# LedMatrix.net
KiCad netlist of a schematic drawn in EAGLE
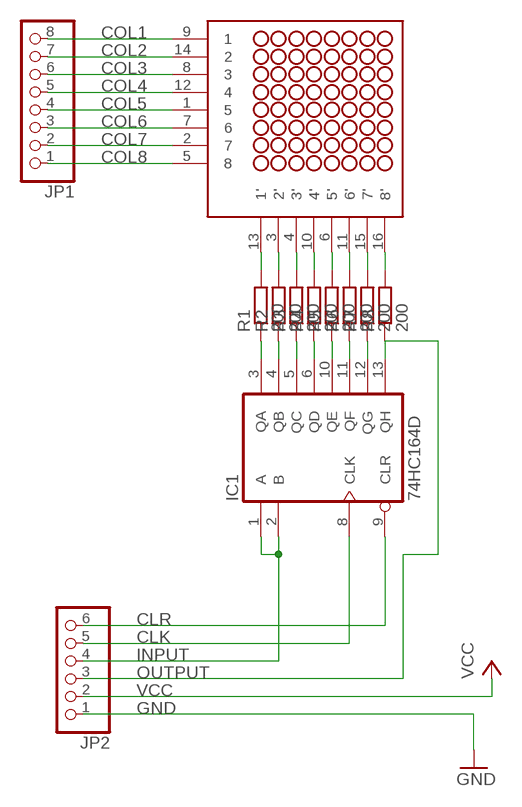
[diagram p0: schematic, sheet 1]

(export (version "E")
  (design (tool "Eeschema 10.0.6"))
  (components
    (comp (ref "IC1")
      (value "74HC164D")
      (footprint "eagle-import:SO14")
      (libsource (lib "eagle-import") (part "74164DHC"))
    )
    (comp (ref "JP1")
      (value "PINHD-1X8")
      (footprint "eagle-import:1X08")
      (libsource (lib "eagle-import") (part "PINHD-1X8"))
    )
    (comp (ref "JP2")
      (value "PINHD-1X6")
      (footprint "eagle-import:1X06")
      (libsource (lib "eagle-import") (part "PINHD-1X6"))
    )
    (comp (ref "R1")
      (value "200")
      (footprint "eagle-import:R1206")
      (libsource (lib "eagle-import") (part "R-EU_R1206"))
    )
    (comp (ref "R2")
      (value "200")
      (footprint "eagle-import:R1206")
      (libsource (lib "eagle-import") (part "R-EU_R1206"))
    )
    (comp (ref "R3")
      (value "200")
      (footprint "eagle-import:R1206")
      (libsource (lib "eagle-import") (part "R-EU_R1206"))
    )
    (comp (ref "R4")
      (value "200")
      (footprint "eagle-import:R1206")
      (libsource (lib "eagle-import") (part "R-EU_R1206"))
    )
    (comp (ref "R5")
      (value "200")
      (footprint "eagle-import:R1206")
      (libsource (lib "eagle-import") (part "R-EU_R1206"))
    )
    (comp (ref "R6")
      (value "200")
      (footprint "eagle-import:R1206")
      (libsource (lib "eagle-import") (part "R-EU_R1206"))
    )
    (comp (ref "R7")
      (value "200")
      (footprint "eagle-import:R1206")
      (libsource (lib "eagle-import") (part "R-EU_R1206"))
    )
    (comp (ref "R8")
      (value "200")
      (footprint "eagle-import:R1206")
      (libsource (lib "eagle-import") (part "R-EU_R1206"))
    )
    (comp (ref "U$1")
      (value "NFM-12881BG-11")
      (footprint "eagle-import:NFM-12881BG-11")
      (libsource (lib "eagle-import") (part "NFM-12881BG-11"))
    )
  )
  (nets
    (net (code "1") (name "/CLK") (class "Default")
      (node (ref "IC1") (pin "8") (pinfunction "CLK_8") (pintype "input"))
      (node (ref "JP2") (pin "5") (pinfunction "5_5") (pintype "passive"))
    )
    (net (code "2") (name "/CLR") (class "Default")
      (node (ref "IC1") (pin "9") (pinfunction "CLR_9") (pintype "input"))
      (node (ref "JP2") (pin "6") (pinfunction "6_6") (pintype "passive"))
    )
    (net (code "3") (name "/COL1") (class "Default")
      (node (ref "JP1") (pin "8") (pinfunction "8_8") (pintype "passive"))
      (node (ref "U$1") (pin "9") (pinfunction "1_9") (pintype "input"))
    )
    (net (code "4") (name "/COL2") (class "Default")
      (node (ref "JP1") (pin "7") (pinfunction "7_7") (pintype "passive"))
      (node (ref "U$1") (pin "14") (pinfunction "2_14") (pintype "input"))
    )
    (net (code "5") (name "/COL3") (class "Default")
      (node (ref "JP1") (pin "6") (pinfunction "6_6") (pintype "passive"))
      (node (ref "U$1") (pin "8") (pinfunction "3_8") (pintype "input"))
    )
    (net (code "6") (name "/COL4") (class "Default")
      (node (ref "JP1") (pin "5") (pinfunction "5_5") (pintype "passive"))
      (node (ref "U$1") (pin "12") (pinfunction "4_12") (pintype "input"))
    )
    (net (code "7") (name "/COL5") (class "Default")
      (node (ref "JP1") (pin "4") (pinfunction "4_4") (pintype "passive"))
      (node (ref "U$1") (pin "1") (pinfunction "5_1") (pintype "input"))
    )
    (net (code "8") (name "/COL6") (class "Default")
      (node (ref "JP1") (pin "3") (pinfunction "3_3") (pintype "passive"))
      (node (ref "U$1") (pin "7") (pinfunction "6_7") (pintype "input"))
    )
    (net (code "9") (name "/COL7") (class "Default")
      (node (ref "JP1") (pin "2") (pinfunction "2_2") (pintype "passive"))
      (node (ref "U$1") (pin "2") (pinfunction "7_2") (pintype "input"))
    )
    (net (code "10") (name "/COL8") (class "Default")
      (node (ref "JP1") (pin "1") (pinfunction "1_1") (pintype "passive"))
      (node (ref "U$1") (pin "5") (pinfunction "8_5") (pintype "input"))
    )
    (net (code "11") (name "/INPUT") (class "Default")
      (node (ref "IC1") (pin "1") (pinfunction "A_1") (pintype "input"))
      (node (ref "IC1") (pin "2") (pinfunction "B_2") (pintype "input"))
      (node (ref "JP2") (pin "4") (pinfunction "4_4") (pintype "passive"))
    )
    (net (code "12") (name "/OUTPUT") (class "Default")
      (node (ref "IC1") (pin "13") (pinfunction "QH_13") (pintype "output"))
      (node (ref "JP2") (pin "3") (pinfunction "3_3") (pintype "passive"))
      (node (ref "R8") (pin "1") (pinfunction "1_1") (pintype "passive"))
    )
    (net (code "13") (name "GND") (class "Default")
      (node (ref "JP2") (pin "1") (pinfunction "1_1") (pintype "passive"))
    )
    (net (code "14") (name "Net-(IC1A-QA)") (class "Default")
      (node (ref "IC1") (pin "3") (pinfunction "QA_3") (pintype "output"))
      (node (ref "R1") (pin "1") (pinfunction "1_1") (pintype "passive"))
    )
    (net (code "15") (name "Net-(IC1A-QB)") (class "Default")
      (node (ref "IC1") (pin "4") (pinfunction "QB_4") (pintype "output"))
      (node (ref "R2") (pin "1") (pinfunction "1_1") (pintype "passive"))
    )
    (net (code "16") (name "Net-(IC1A-QC)") (class "Default")
      (node (ref "IC1") (pin "5") (pinfunction "QC_5") (pintype "output"))
      (node (ref "R3") (pin "1") (pinfunction "1_1") (pintype "passive"))
    )
    (net (code "17") (name "Net-(IC1A-QD)") (class "Default")
      (node (ref "IC1") (pin "6") (pinfunction "QD_6") (pintype "output"))
      (node (ref "R4") (pin "1") (pinfunction "1_1") (pintype "passive"))
    )
    (net (code "18") (name "Net-(IC1A-QE)") (class "Default")
      (node (ref "IC1") (pin "10") (pinfunction "QE_10") (pintype "output"))
      (node (ref "R5") (pin "1") (pinfunction "1_1") (pintype "passive"))
    )
    (net (code "19") (name "Net-(IC1A-QF)") (class "Default")
      (node (ref "IC1") (pin "11") (pinfunction "QF_11") (pintype "output"))
      (node (ref "R6") (pin "1") (pinfunction "1_1") (pintype "passive"))
    )
    (net (code "20") (name "Net-(IC1A-QG)") (class "Default")
      (node (ref "IC1") (pin "12") (pinfunction "QG_12") (pintype "output"))
      (node (ref "R7") (pin "1") (pinfunction "1_1") (pintype "passive"))
    )
    (net (code "21") (name "Net-(U$1-1')") (class "Default")
      (node (ref "R1") (pin "2") (pinfunction "2_2") (pintype "passive"))
      (node (ref "U$1") (pin "13") (pinfunction "1'_13") (pintype "output"))
    )
    (net (code "22") (name "Net-(U$1-2')") (class "Default")
      (node (ref "R2") (pin "2") (pinfunction "2_2") (pintype "passive"))
      (node (ref "U$1") (pin "3") (pinfunction "2'_3") (pintype "output"))
    )
    (net (code "23") (name "Net-(U$1-3')") (class "Default")
      (node (ref "R3") (pin "2") (pinfunction "2_2") (pintype "passive"))
      (node (ref "U$1") (pin "4") (pinfunction "3'_4") (pintype "output"))
    )
    (net (code "24") (name "Net-(U$1-4')") (class "Default")
      (node (ref "R4") (pin "2") (pinfunction "2_2") (pintype "passive"))
      (node (ref "U$1") (pin "10") (pinfunction "4'_10") (pintype "output"))
    )
    (net (code "25") (name "Net-(U$1-5')") (class "Default")
      (node (ref "R5") (pin "2") (pinfunction "2_2") (pintype "passive"))
      (node (ref "U$1") (pin "6") (pinfunction "5'_6") (pintype "output"))
    )
    (net (code "26") (name "Net-(U$1-6')") (class "Default")
      (node (ref "R6") (pin "2") (pinfunction "2_2") (pintype "passive"))
      (node (ref "U$1") (pin "11") (pinfunction "6'_11") (pintype "output"))
    )
    (net (code "27") (name "Net-(U$1-7')") (class "Default")
      (node (ref "R7") (pin "2") (pinfunction "2_2") (pintype "passive"))
      (node (ref "U$1") (pin "15") (pinfunction "7'_15") (pintype "output"))
    )
    (net (code "28") (name "Net-(U$1-8')") (class "Default")
      (node (ref "R8") (pin "2") (pinfunction "2_2") (pintype "passive"))
      (node (ref "U$1") (pin "16") (pinfunction "8'_16") (pintype "output"))
    )
    (net (code "29") (name "VCC") (class "Default")
      (node (ref "JP2") (pin "2") (pinfunction "2_2") (pintype "passive"))
    )
  )
)
